# atx-breakout.net
KiCad netlist of a schematic drawn in EAGLE
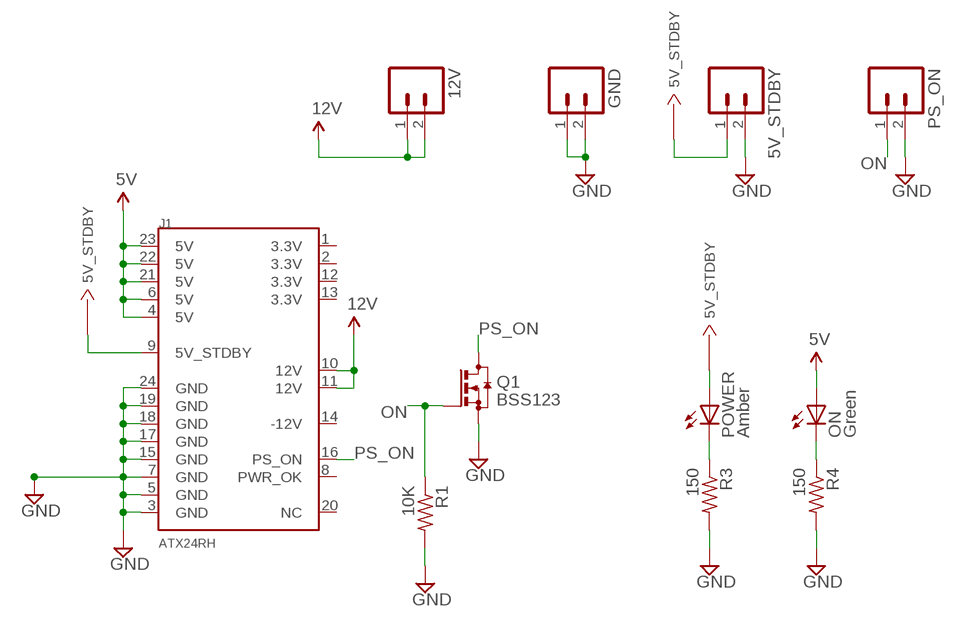
[diagram p0: schematic, sheet 1]

(export (version "E")
  (design (tool "Eeschema 10.0.6"))
  (components
    (comp (ref "5V_STDBY")
      (value "M025MM")
      (footprint "eagle-import:SCREWTERMINAL-5MM-2")
      (libsource (lib "eagle-import") (part "M025MM"))
    )
    (comp (ref "12V")
      (value "M025MM")
      (footprint "eagle-import:SCREWTERMINAL-5MM-2")
      (libsource (lib "eagle-import") (part "M025MM"))
    )
    (comp (ref "GND")
      (value "M025MM")
      (footprint "eagle-import:SCREWTERMINAL-5MM-2")
      (libsource (lib "eagle-import") (part "M025MM"))
    )
    (comp (ref "J1")
      (value "ATX24RH")
      (footprint "eagle-import:ATX24_RIGHT_ANGLE")
      (libsource (lib "eagle-import") (part "ATX24RH"))
    )
    (comp (ref "ON")
      (value "Green")
      (footprint "eagle-import:CHIP-LED0805")
      (libsource (lib "eagle-import") (part "LEDCHIP-LED0805"))
    )
    (comp (ref "POWER")
      (value "Amber")
      (footprint "eagle-import:CHIP-LED0805")
      (libsource (lib "eagle-import") (part "LEDCHIP-LED0805"))
    )
    (comp (ref "PS_ON")
      (value "M025MM")
      (footprint "eagle-import:SCREWTERMINAL-5MM-2")
      (libsource (lib "eagle-import") (part "M025MM"))
    )
    (comp (ref "Q1")
      (value "BSS123")
      (footprint "eagle-import:SOT23")
      (libsource (lib "eagle-import") (part "BSS123"))
    )
    (comp (ref "R1")
      (value "10K")
      (footprint "eagle-import:R0805")
      (libsource (lib "eagle-import") (part "R-US_R0805"))
    )
    (comp (ref "R3")
      (value "150")
      (footprint "eagle-import:R0805")
      (libsource (lib "eagle-import") (part "R-US_R0805"))
    )
    (comp (ref "R4")
      (value "150")
      (footprint "eagle-import:R0805")
      (libsource (lib "eagle-import") (part "R-US_R0805"))
    )
  )
  (nets
    (net (code "1") (name "/ON") (class "Default")
      (node (ref "PS_ON") (pin "1") (pinfunction "1_1") (pintype "passive"))
      (node (ref "Q1") (pin "1") (pinfunction "G_1") (pintype "passive"))
      (node (ref "R1") (pin "1") (pinfunction "1_1") (pintype "passive"))
    )
    (net (code "2") (name "/PS_ON") (class "Default")
      (node (ref "J1") (pin "16") (pinfunction "PS_ON_16") (pintype "bidirectional"))
      (node (ref "Q1") (pin "3") (pinfunction "D_3") (pintype "passive"))
    )
    (net (code "3") (name "5V") (class "Default")
      (node (ref "J1") (pin "21") (pinfunction "5V_21") (pintype "bidirectional"))
      (node (ref "J1") (pin "22") (pinfunction "5V_22") (pintype "bidirectional"))
      (node (ref "J1") (pin "23") (pinfunction "5V_23") (pintype "bidirectional"))
      (node (ref "J1") (pin "4") (pinfunction "5V_4") (pintype "bidirectional"))
      (node (ref "J1") (pin "6") (pinfunction "5V_6") (pintype "bidirectional"))
      (node (ref "ON") (pin "A") (pinfunction "A_A") (pintype "passive"))
    )
    (net (code "4") (name "5V_STDBY") (class "Default")
      (node (ref "5V_STDBY") (pin "1") (pinfunction "1_1") (pintype "passive"))
      (node (ref "J1") (pin "9") (pinfunction "5V_STDBY_9") (pintype "bidirectional"))
      (node (ref "POWER") (pin "A") (pinfunction "A_A") (pintype "passive"))
    )
    (net (code "5") (name "12V") (class "Default")
      (node (ref "12V") (pin "1") (pinfunction "1_1") (pintype "passive"))
      (node (ref "12V") (pin "2") (pinfunction "2_2") (pintype "passive"))
      (node (ref "J1") (pin "10") (pinfunction "12V_10") (pintype "bidirectional"))
      (node (ref "J1") (pin "11") (pinfunction "12V_11") (pintype "bidirectional"))
    )
    (net (code "6") (name "GND") (class "Default")
      (node (ref "5V_STDBY") (pin "2") (pinfunction "2_2") (pintype "passive"))
      (node (ref "GND") (pin "1") (pinfunction "1_1") (pintype "passive"))
      (node (ref "GND") (pin "2") (pinfunction "2_2") (pintype "passive"))
      (node (ref "J1") (pin "15") (pinfunction "GND_15") (pintype "bidirectional"))
      (node (ref "J1") (pin "17") (pinfunction "GND_17") (pintype "bidirectional"))
      (node (ref "J1") (pin "18") (pinfunction "GND_18") (pintype "bidirectional"))
      (node (ref "J1") (pin "19") (pinfunction "GND_19") (pintype "bidirectional"))
      (node (ref "J1") (pin "24") (pinfunction "GND_24") (pintype "bidirectional"))
      (node (ref "J1") (pin "3") (pinfunction "GND_3") (pintype "bidirectional"))
      (node (ref "J1") (pin "5") (pinfunction "GND_5") (pintype "bidirectional"))
      (node (ref "J1") (pin "7") (pinfunction "GND_7") (pintype "bidirectional"))
      (node (ref "PS_ON") (pin "2") (pinfunction "2_2") (pintype "passive"))
      (node (ref "Q1") (pin "2") (pinfunction "S_2") (pintype "passive"))
      (node (ref "R1") (pin "2") (pinfunction "2_2") (pintype "passive"))
      (node (ref "R3") (pin "2") (pinfunction "2_2") (pintype "passive"))
      (node (ref "R4") (pin "2") (pinfunction "2_2") (pintype "passive"))
    )
    (net (code "7") (name "Net-(ON-PadC)") (class "Default")
      (node (ref "ON") (pin "C") (pinfunction "C_C") (pintype "passive"))
      (node (ref "R4") (pin "1") (pinfunction "1_1") (pintype "passive"))
    )
    (net (code "8") (name "Net-(POWER-PadC)") (class "Default")
      (node (ref "POWER") (pin "C") (pinfunction "C_C") (pintype "passive"))
      (node (ref "R3") (pin "1") (pinfunction "1_1") (pintype "passive"))
    )
    (net (code "9") (name "unconnected-(J1--12V-Pad14)") (class "Default")
      (node (ref "J1") (pin "14") (pinfunction "-12V_14") (pintype "bidirectional"))
    )
    (net (code "10") (name "unconnected-(J1-3.3V-Pad1)") (class "Default")
      (node (ref "J1") (pin "1") (pinfunction "3.3V_1") (pintype "bidirectional"))
    )
    (net (code "11") (name "unconnected-(J1-3.3V-Pad2)") (class "Default")
      (node (ref "J1") (pin "2") (pinfunction "3.3V_2") (pintype "bidirectional"))
    )
    (net (code "12") (name "unconnected-(J1-3.3V-Pad12)") (class "Default")
      (node (ref "J1") (pin "12") (pinfunction "3.3V_12") (pintype "bidirectional"))
    )
    (net (code "13") (name "unconnected-(J1-3.3V-Pad13)") (class "Default")
      (node (ref "J1") (pin "13") (pinfunction "3.3V_13") (pintype "bidirectional"))
    )
    (net (code "14") (name "unconnected-(J1-NC-Pad20)") (class "Default")
      (node (ref "J1") (pin "20") (pinfunction "NC_20") (pintype "bidirectional"))
    )
    (net (code "15") (name "unconnected-(J1-PWR_OK-Pad8)") (class "Default")
      (node (ref "J1") (pin "8") (pinfunction "PWR_OK_8") (pintype "bidirectional"))
    )
  )
)
